# 5_-CONNECTORS.net
KiCad netlist of a schematic drawn in Altium Designer
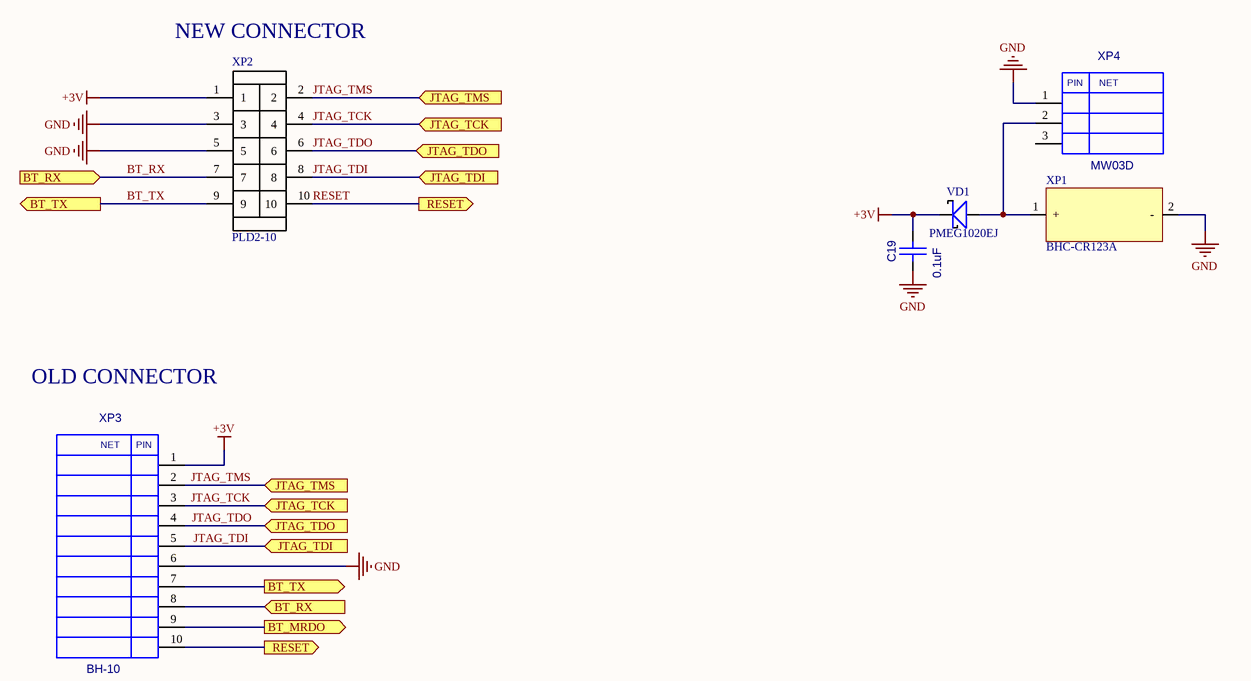
[diagram p0: [5]-CONNECTORS.SchDoc]

(export (version "E")
  (design (tool "Eeschema 10.0.6"))
  (components
    (comp (ref "C19")
      (value "0.1uF")
      (footprint "CC0603")
      (description "CC0603")
      (libsource (lib "fizik_lib") (part "CC0603"))
    )
    (comp (ref "VD1")
      (value "PMEG1020EJ")
      (footprint "SOD323")
      (libsource (lib "fizik_lib") (part "PMEG2010"))
    )
    (comp (ref "XP1")
      (value "BHC-CR123A")
      (footprint "CR123_HOLDER")
      (description "Holder for CR123 battery")
      (libsource (lib "fizik_lib") (part "BHC-CR123A"))
    )
    (comp (ref "XP2")
      (value "PLD2-10")
      (footprint "PLD2-10")
      (libsource (lib "gprs_modem_2") (part "PLD2-10"))
    )
    (comp (ref "XP3") (value "BH-10") (footprint "BH-10") (libsource (lib "gprs_modem_2") (part "BH-10")))
    (comp (ref "XP4") (value "MW03D") (footprint "MW03D") (libsource (lib "gprs_modem_2") (part "MW03D")))
  )
  (nets
    (net (code "1") (name "+3V") (class "Default")
      (node (ref "C19") (pin "2") (pinfunction "B_2") (pintype "passive"))
      (node (ref "VD1") (pin "2") (pinfunction "K_2") (pintype "passive"))
      (node (ref "XP2") (pin "1") (pinfunction "1_1") (pintype "passive"))
      (node (ref "XP3") (pin "1") (pinfunction "1_1") (pintype "passive"))
    )
    (net (code "2") (name "/BT_MRDO") (class "Default")
      (node (ref "XP3") (pin "9") (pinfunction "9_9") (pintype "passive"))
    )
    (net (code "3") (name "/BT_RX") (class "Default")
      (node (ref "XP2") (pin "7") (pinfunction "7_7") (pintype "passive"))
      (node (ref "XP3") (pin "8") (pinfunction "8_8") (pintype "passive"))
    )
    (net (code "4") (name "/BT_TX") (class "Default")
      (node (ref "XP2") (pin "9") (pinfunction "9_9") (pintype "passive"))
      (node (ref "XP3") (pin "7") (pinfunction "7_7") (pintype "passive"))
    )
    (net (code "5") (name "/JTAG_TCK") (class "Default")
      (node (ref "XP2") (pin "4") (pinfunction "4_4") (pintype "passive"))
      (node (ref "XP3") (pin "3") (pinfunction "3_3") (pintype "passive"))
    )
    (net (code "6") (name "/JTAG_TDI") (class "Default")
      (node (ref "XP2") (pin "8") (pinfunction "8_8") (pintype "passive"))
      (node (ref "XP3") (pin "5") (pinfunction "5_5") (pintype "passive"))
    )
    (net (code "7") (name "/JTAG_TDO") (class "Default")
      (node (ref "XP2") (pin "6") (pinfunction "6_6") (pintype "passive"))
      (node (ref "XP3") (pin "4") (pinfunction "4_4") (pintype "passive"))
    )
    (net (code "8") (name "/JTAG_TMS") (class "Default")
      (node (ref "XP2") (pin "2") (pinfunction "2_2") (pintype "passive"))
      (node (ref "XP3") (pin "2") (pinfunction "2_2") (pintype "passive"))
    )
    (net (code "9") (name "/RESET") (class "Default")
      (node (ref "XP2") (pin "10") (pinfunction "10_10") (pintype "passive"))
      (node (ref "XP3") (pin "10") (pinfunction "10_10") (pintype "passive"))
    )
    (net (code "10") (name "GND") (class "Default")
      (node (ref "C19") (pin "1") (pinfunction "A_1") (pintype "passive"))
      (node (ref "XP1") (pin "2") (pinfunction "-_2") (pintype "passive"))
      (node (ref "XP2") (pin "3") (pinfunction "3_3") (pintype "passive"))
      (node (ref "XP2") (pin "5") (pinfunction "5_5") (pintype "passive"))
      (node (ref "XP3") (pin "6") (pinfunction "6_6") (pintype "passive"))
      (node (ref "XP4") (pin "1") (pinfunction "1_1") (pintype "passive"))
    )
    (net (code "11") (name "Net-(VD1-A)") (class "Default")
      (node (ref "VD1") (pin "1") (pinfunction "A_1") (pintype "passive"))
      (node (ref "XP1") (pin "1") (pinfunction "+_1") (pintype "passive"))
      (node (ref "XP4") (pin "2") (pinfunction "2_2") (pintype "passive"))
    )
    (net (code "12") (name "unconnected-(XP4-Pad3)") (class "Default")
      (node (ref "XP4") (pin "3") (pinfunction "3_3") (pintype "passive"))
    )
  )
)
